# SRAM_256Kx32_TSOP44_1.net
KiCad netlist of a schematic drawn in Altium Designer
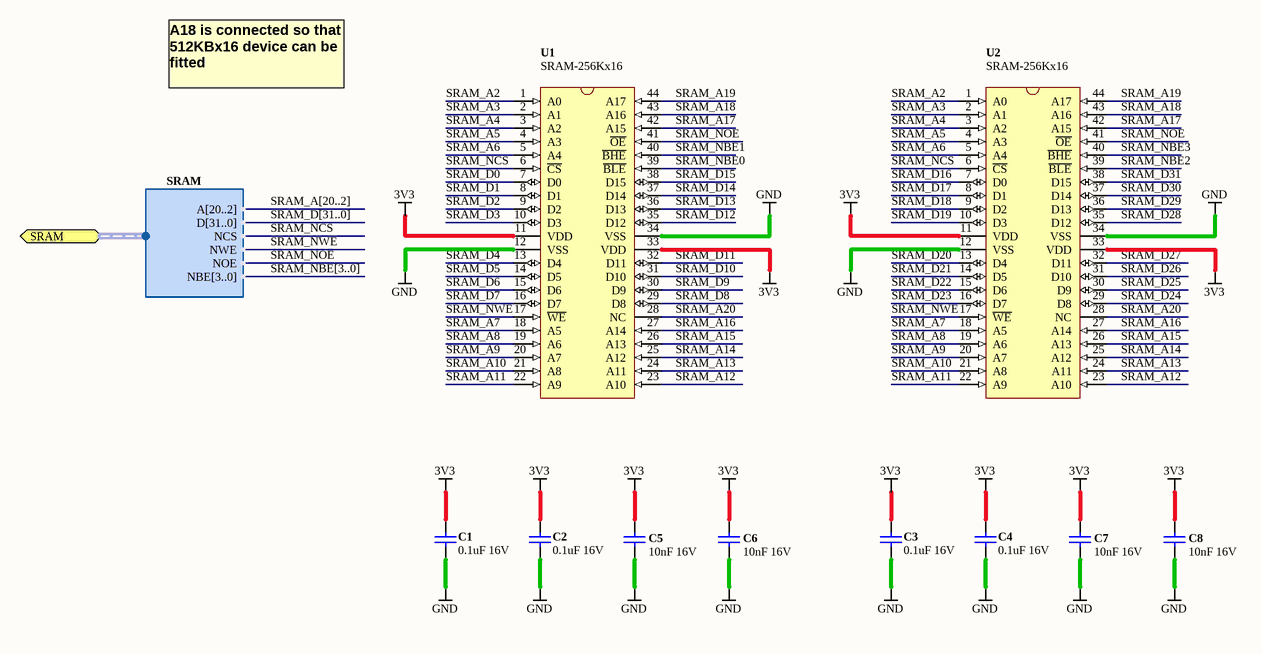
[diagram p0: SRAM_256Kx32_TSOP44_1.SchDoc]

(export (version "E")
  (design (tool "Eeschema 10.0.6"))
  (components
    (comp (ref "C1")
      (value "0.1uF 16V")
      (footprint "CAPC1005-STAR")
      (description "Capacitor, Ceramic, 0.1uF 10% 16V 0402 (1005) X7R")
      (fields (field (name "TOLERANCE") "10 %"))
      (libsource (lib "altium-import") (part "root_0_mirrored_CAP-NP_"))
    )
    (comp (ref "C2")
      (value "0.1uF 16V")
      (footprint "CAPC1005-STAR")
      (description "Capacitor, Ceramic, 0.1uF 10% 16V 0402 (1005) X7R")
      (fields (field (name "TOLERANCE") "10 %"))
      (libsource (lib "altium-import") (part "root_0_mirrored_CAP-NP_"))
    )
    (comp (ref "C3")
      (value "0.1uF 16V")
      (footprint "CAPC1005-STAR")
      (description "Capacitor, Ceramic, 0.1uF 10% 16V 0402 (1005) X7R")
      (fields (field (name "TOLERANCE") "10 %"))
      (libsource (lib "altium-import") (part "root_0_mirrored_CAP-NP_"))
    )
    (comp (ref "C4")
      (value "0.1uF 16V")
      (footprint "CAPC1005-STAR")
      (description "Capacitor, Ceramic, 0.1uF 10% 16V 0402 (1005) X7R")
      (fields (field (name "TOLERANCE") "10 %"))
      (libsource (lib "altium-import") (part "root_0_mirrored_CAP-NP_"))
    )
    (comp (ref "C5")
      (value "10nF 16V")
      (footprint "CAPC1005-STAR")
      (description "Capacitor, Ceramic, 10nF 10% 16V 0402 (1005) X7R")
      (fields (field (name "TOLERANCE") "10 %"))
      (libsource (lib "altium-import") (part "root_0_CAP-NP_"))
    )
    (comp (ref "C6")
      (value "10nF 16V")
      (footprint "CAPC1005-STAR")
      (description "Capacitor, Ceramic, 10nF 10% 16V 0402 (1005) X7R")
      (fields (field (name "TOLERANCE") "10 %"))
      (libsource (lib "altium-import") (part "root_0_CAP-NP_"))
    )
    (comp (ref "C7")
      (value "10nF 16V")
      (footprint "CAPC1005-STAR")
      (description "Capacitor, Ceramic, 10nF 10% 16V 0402 (1005) X7R")
      (fields (field (name "TOLERANCE") "10 %"))
      (libsource (lib "altium-import") (part "root_0_CAP-NP_"))
    )
    (comp (ref "C8")
      (value "10nF 16V")
      (footprint "CAPC1005-STAR")
      (description "Capacitor, Ceramic, 10nF 10% 16V 0402 (1005) X7R")
      (fields (field (name "TOLERANCE") "10 %"))
      (libsource (lib "altium-import") (part "root_0_CAP-NP_"))
    )
    (comp (ref "U1")
      (value "SRAM-256Kx16")
      (footprint "TSOP80P1176-44")
      (description "K6R4016V1D-TC10T, 256K x 16-Bit SRAM, TSOP44")
      (libsource (lib "altium-import") (part "root_0_K6R4016V1D-T_"))
    )
    (comp (ref "U2")
      (value "SRAM-256Kx16")
      (footprint "TSOP80P1176-44")
      (description "K6R4016V1D-TC10T, 256K x 16-Bit SRAM, TSOP44")
      (libsource (lib "altium-import") (part "root_0_K6R4016V1D-T_"))
    )
  )
  (nets
    (net (code "2") (name "/SRAM_A2") (class "Default")
      (node (ref "U1") (pin "1") (pinfunction "A0_1") (pintype "input"))
      (node (ref "U2") (pin "1") (pinfunction "A0_1") (pintype "input"))
    )
    (net (code "3") (name "/SRAM_A3") (class "Default")
      (node (ref "U1") (pin "2") (pinfunction "A1_2") (pintype "input"))
      (node (ref "U2") (pin "2") (pinfunction "A1_2") (pintype "input"))
    )
    (net (code "4") (name "/SRAM_A4") (class "Default")
      (node (ref "U1") (pin "3") (pinfunction "A2_3") (pintype "input"))
      (node (ref "U2") (pin "3") (pinfunction "A2_3") (pintype "input"))
    )
    (net (code "5") (name "/SRAM_A5") (class "Default")
      (node (ref "U1") (pin "4") (pinfunction "A3_4") (pintype "input"))
      (node (ref "U2") (pin "4") (pinfunction "A3_4") (pintype "input"))
    )
    (net (code "6") (name "/SRAM_A6") (class "Default")
      (node (ref "U1") (pin "5") (pinfunction "A4_5") (pintype "input"))
      (node (ref "U2") (pin "5") (pinfunction "A4_5") (pintype "input"))
    )
    (net (code "7") (name "/SRAM_A7") (class "Default")
      (node (ref "U1") (pin "18") (pinfunction "A5_18") (pintype "input"))
      (node (ref "U2") (pin "18") (pinfunction "A5_18") (pintype "input"))
    )
    (net (code "8") (name "/SRAM_A8") (class "Default")
      (node (ref "U1") (pin "19") (pinfunction "A6_19") (pintype "input"))
      (node (ref "U2") (pin "19") (pinfunction "A6_19") (pintype "input"))
    )
    (net (code "9") (name "/SRAM_A9") (class "Default")
      (node (ref "U1") (pin "20") (pinfunction "A7_20") (pintype "input"))
      (node (ref "U2") (pin "20") (pinfunction "A7_20") (pintype "input"))
    )
    (net (code "10") (name "/SRAM_A10") (class "Default")
      (node (ref "U1") (pin "21") (pinfunction "A8_21") (pintype "input"))
      (node (ref "U2") (pin "21") (pinfunction "A8_21") (pintype "input"))
    )
    (net (code "11") (name "/SRAM_A11") (class "Default")
      (node (ref "U1") (pin "22") (pinfunction "A9_22") (pintype "input"))
      (node (ref "U2") (pin "22") (pinfunction "A9_22") (pintype "input"))
    )
    (net (code "12") (name "/SRAM_A12") (class "Default")
      (node (ref "U1") (pin "23") (pinfunction "A10_23") (pintype "input"))
      (node (ref "U2") (pin "23") (pinfunction "A10_23") (pintype "input"))
    )
    (net (code "13") (name "/SRAM_A13") (class "Default")
      (node (ref "U1") (pin "24") (pinfunction "A11_24") (pintype "input"))
      (node (ref "U2") (pin "24") (pinfunction "A11_24") (pintype "input"))
    )
    (net (code "14") (name "/SRAM_A14") (class "Default")
      (node (ref "U1") (pin "25") (pinfunction "A12_25") (pintype "input"))
      (node (ref "U2") (pin "25") (pinfunction "A12_25") (pintype "input"))
    )
    (net (code "15") (name "/SRAM_A15") (class "Default")
      (node (ref "U1") (pin "26") (pinfunction "A13_26") (pintype "input"))
      (node (ref "U2") (pin "26") (pinfunction "A13_26") (pintype "input"))
    )
    (net (code "16") (name "/SRAM_A16") (class "Default")
      (node (ref "U1") (pin "27") (pinfunction "A14_27") (pintype "input"))
      (node (ref "U2") (pin "27") (pinfunction "A14_27") (pintype "input"))
    )
    (net (code "17") (name "/SRAM_A17") (class "Default")
      (node (ref "U1") (pin "42") (pinfunction "A15_42") (pintype "input"))
      (node (ref "U2") (pin "42") (pinfunction "A15_42") (pintype "input"))
    )
    (net (code "18") (name "/SRAM_A18") (class "Default")
      (node (ref "U1") (pin "43") (pinfunction "A16_43") (pintype "input"))
      (node (ref "U2") (pin "43") (pinfunction "A16_43") (pintype "input"))
    )
    (net (code "19") (name "/SRAM_A19") (class "Default")
      (node (ref "U1") (pin "44") (pinfunction "A17_44") (pintype "input"))
      (node (ref "U2") (pin "44") (pinfunction "A17_44") (pintype "input"))
    )
    (net (code "20") (name "/SRAM_A20") (class "Default")
      (node (ref "U1") (pin "28") (pinfunction "NC_28") (pintype "passive"))
      (node (ref "U2") (pin "28") (pinfunction "NC_28") (pintype "passive"))
    )
    (net (code "22") (name "/SRAM_D0") (class "Default")
      (node (ref "U1") (pin "7") (pinfunction "D0_7") (pintype "bidirectional"))
    )
    (net (code "23") (name "/SRAM_D1") (class "Default")
      (node (ref "U1") (pin "8") (pinfunction "D1_8") (pintype "bidirectional"))
    )
    (net (code "24") (name "/SRAM_D2") (class "Default")
      (node (ref "U1") (pin "9") (pinfunction "D2_9") (pintype "bidirectional"))
    )
    (net (code "25") (name "/SRAM_D3") (class "Default")
      (node (ref "U1") (pin "10") (pinfunction "D3_10") (pintype "bidirectional"))
    )
    (net (code "26") (name "/SRAM_D4") (class "Default")
      (node (ref "U1") (pin "13") (pinfunction "D4_13") (pintype "bidirectional"))
    )
    (net (code "27") (name "/SRAM_D5") (class "Default")
      (node (ref "U1") (pin "14") (pinfunction "D5_14") (pintype "bidirectional"))
    )
    (net (code "28") (name "/SRAM_D6") (class "Default")
      (node (ref "U1") (pin "15") (pinfunction "D6_15") (pintype "bidirectional"))
    )
    (net (code "29") (name "/SRAM_D7") (class "Default")
      (node (ref "U1") (pin "16") (pinfunction "D7_16") (pintype "bidirectional"))
    )
    (net (code "30") (name "/SRAM_D8") (class "Default")
      (node (ref "U1") (pin "29") (pinfunction "D8_29") (pintype "bidirectional"))
    )
    (net (code "31") (name "/SRAM_D9") (class "Default")
      (node (ref "U1") (pin "30") (pinfunction "D9_30") (pintype "bidirectional"))
    )
    (net (code "32") (name "/SRAM_D10") (class "Default")
      (node (ref "U1") (pin "31") (pinfunction "D10_31") (pintype "bidirectional"))
    )
    (net (code "33") (name "/SRAM_D11") (class "Default")
      (node (ref "U1") (pin "32") (pinfunction "D11_32") (pintype "bidirectional"))
    )
    (net (code "34") (name "/SRAM_D12") (class "Default")
      (node (ref "U1") (pin "35") (pinfunction "D12_35") (pintype "bidirectional"))
    )
    (net (code "35") (name "/SRAM_D13") (class "Default")
      (node (ref "U1") (pin "36") (pinfunction "D13_36") (pintype "bidirectional"))
    )
    (net (code "36") (name "/SRAM_D14") (class "Default")
      (node (ref "U1") (pin "37") (pinfunction "D14_37") (pintype "bidirectional"))
    )
    (net (code "37") (name "/SRAM_D15") (class "Default")
      (node (ref "U1") (pin "38") (pinfunction "D15_38") (pintype "bidirectional"))
    )
    (net (code "38") (name "/SRAM_D16") (class "Default")
      (node (ref "U2") (pin "7") (pinfunction "D0_7") (pintype "bidirectional"))
    )
    (net (code "39") (name "/SRAM_D17") (class "Default")
      (node (ref "U2") (pin "8") (pinfunction "D1_8") (pintype "bidirectional"))
    )
    (net (code "40") (name "/SRAM_D18") (class "Default")
      (node (ref "U2") (pin "9") (pinfunction "D2_9") (pintype "bidirectional"))
    )
    (net (code "41") (name "/SRAM_D19") (class "Default")
      (node (ref "U2") (pin "10") (pinfunction "D3_10") (pintype "bidirectional"))
    )
    (net (code "42") (name "/SRAM_D20") (class "Default")
      (node (ref "U2") (pin "13") (pinfunction "D4_13") (pintype "bidirectional"))
    )
    (net (code "43") (name "/SRAM_D21") (class "Default")
      (node (ref "U2") (pin "14") (pinfunction "D5_14") (pintype "bidirectional"))
    )
    (net (code "44") (name "/SRAM_D22") (class "Default")
      (node (ref "U2") (pin "15") (pinfunction "D6_15") (pintype "bidirectional"))
    )
    (net (code "45") (name "/SRAM_D23") (class "Default")
      (node (ref "U2") (pin "16") (pinfunction "D7_16") (pintype "bidirectional"))
    )
    (net (code "46") (name "/SRAM_D24") (class "Default")
      (node (ref "U2") (pin "29") (pinfunction "D8_29") (pintype "bidirectional"))
    )
    (net (code "47") (name "/SRAM_D25") (class "Default")
      (node (ref "U2") (pin "30") (pinfunction "D9_30") (pintype "bidirectional"))
    )
    (net (code "48") (name "/SRAM_D26") (class "Default")
      (node (ref "U2") (pin "31") (pinfunction "D10_31") (pintype "bidirectional"))
    )
    (net (code "49") (name "/SRAM_D27") (class "Default")
      (node (ref "U2") (pin "32") (pinfunction "D11_32") (pintype "bidirectional"))
    )
    (net (code "50") (name "/SRAM_D28") (class "Default")
      (node (ref "U2") (pin "35") (pinfunction "D12_35") (pintype "bidirectional"))
    )
    (net (code "51") (name "/SRAM_D29") (class "Default")
      (node (ref "U2") (pin "36") (pinfunction "D13_36") (pintype "bidirectional"))
    )
    (net (code "52") (name "/SRAM_D30") (class "Default")
      (node (ref "U2") (pin "37") (pinfunction "D14_37") (pintype "bidirectional"))
    )
    (net (code "53") (name "/SRAM_D31") (class "Default")
      (node (ref "U2") (pin "38") (pinfunction "D15_38") (pintype "bidirectional"))
    )
    (net (code "55") (name "/SRAM_NBE0") (class "Default")
      (node (ref "U1") (pin "39") (pinfunction "~{BLE}_39") (pintype "input"))
    )
    (net (code "56") (name "/SRAM_NBE1") (class "Default")
      (node (ref "U1") (pin "40") (pinfunction "~{BHE}_40") (pintype "input"))
    )
    (net (code "57") (name "/SRAM_NBE2") (class "Default")
      (node (ref "U2") (pin "39") (pinfunction "~{BLE}_39") (pintype "input"))
    )
    (net (code "58") (name "/SRAM_NBE3") (class "Default")
      (node (ref "U2") (pin "40") (pinfunction "~{BHE}_40") (pintype "input"))
    )
    (net (code "60") (name "/SRAM_NCS") (class "Default")
      (node (ref "U1") (pin "6") (pinfunction "~{CS}_6") (pintype "input"))
      (node (ref "U2") (pin "6") (pinfunction "~{CS}_6") (pintype "input"))
    )
    (net (code "61") (name "/SRAM_NOE") (class "Default")
      (node (ref "U1") (pin "41") (pinfunction "~{OE}_41") (pintype "input"))
      (node (ref "U2") (pin "41") (pinfunction "~{OE}_41") (pintype "input"))
    )
    (net (code "62") (name "/SRAM_NWE") (class "Default")
      (node (ref "U1") (pin "17") (pinfunction "~{WE}_17") (pintype "input"))
      (node (ref "U2") (pin "17") (pinfunction "~{WE}_17") (pintype "input"))
    )
    (net (code "64") (name "3V3") (class "Default")
      (node (ref "C1") (pin "1") (pinfunction "1_1") (pintype "passive"))
      (node (ref "C2") (pin "1") (pinfunction "1_1") (pintype "passive"))
      (node (ref "C3") (pin "1") (pinfunction "1_1") (pintype "passive"))
      (node (ref "C4") (pin "1") (pinfunction "1_1") (pintype "passive"))
      (node (ref "C5") (pin "1") (pinfunction "1_1") (pintype "passive"))
      (node (ref "C6") (pin "1") (pinfunction "1_1") (pintype "passive"))
      (node (ref "C7") (pin "1") (pinfunction "1_1") (pintype "passive"))
      (node (ref "C8") (pin "1") (pinfunction "1_1") (pintype "passive"))
      (node (ref "U1") (pin "11") (pinfunction "VDD_11") (pintype "power_in"))
      (node (ref "U1") (pin "33") (pinfunction "VDD_33") (pintype "power_in"))
      (node (ref "U2") (pin "11") (pinfunction "VDD_11") (pintype "power_in"))
      (node (ref "U2") (pin "33") (pinfunction "VDD_33") (pintype "power_in"))
    )
    (net (code "65") (name "GND") (class "Default")
      (node (ref "C1") (pin "2") (pinfunction "2_2") (pintype "passive"))
      (node (ref "C2") (pin "2") (pinfunction "2_2") (pintype "passive"))
      (node (ref "C3") (pin "2") (pinfunction "2_2") (pintype "passive"))
      (node (ref "C4") (pin "2") (pinfunction "2_2") (pintype "passive"))
      (node (ref "C5") (pin "2") (pinfunction "2_2") (pintype "passive"))
      (node (ref "C6") (pin "2") (pinfunction "2_2") (pintype "passive"))
      (node (ref "C7") (pin "2") (pinfunction "2_2") (pintype "passive"))
      (node (ref "C8") (pin "2") (pinfunction "2_2") (pintype "passive"))
      (node (ref "U1") (pin "12") (pinfunction "VSS_12") (pintype "power_in"))
      (node (ref "U1") (pin "34") (pinfunction "VSS_34") (pintype "power_in"))
      (node (ref "U2") (pin "12") (pinfunction "VSS_12") (pintype "power_in"))
      (node (ref "U2") (pin "34") (pinfunction "VSS_34") (pintype "power_in"))
    )
  )
)
